# SM1_System.net
KiCad netlist of a schematic drawn in Altium Designer
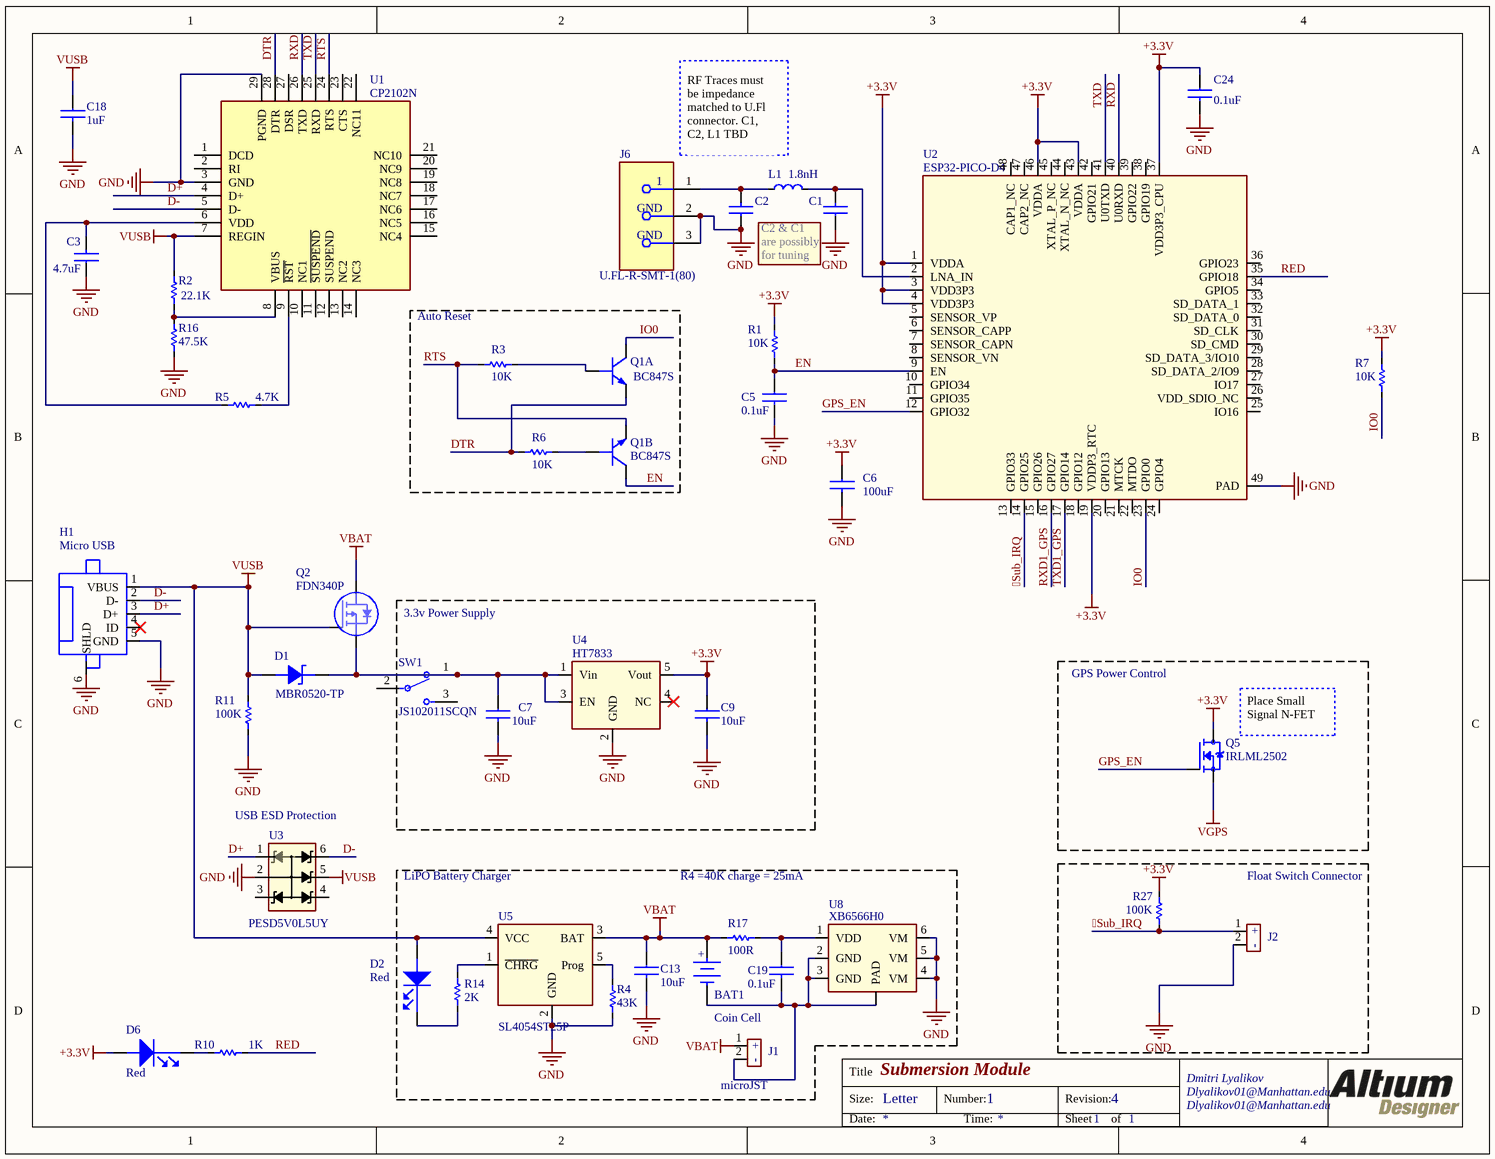
[diagram p0: SM1_System.SchDoc]

(export (version "E")
  (design (tool "Eeschema 10.0.6"))
  (components
    (comp (ref "BAT1")
      (value "BATTERY-HOLDER (2450)")
      (footprint "BU2450SM-JJ-GTR")
      (description "HOLDER,BATT,COIN,24.5MM,SMT")
      (fields (field (name "PARTNUMBER") "BU2450SM-JJ-GTR") (field (name "MANUFACTURER") "MPD"))
      (libsource (lib "MAR") (part "BU2450SM-JJ-GTR"))
    )
    (comp (ref "C1")
      (value "~")
      (footprint "CAPC1005X56N")
      (description "DNP")
      (libsource (lib "MAR") (part "CAP_0402"))
    )
    (comp (ref "C2")
      (value "~")
      (footprint "CAPC1005X56N")
      (description "DNP")
      (libsource (lib "MAR") (part "CAP_0402"))
    )
    (comp (ref "C3")
      (value "4.7uF")
      (footprint "CAPC1005X56N")
      (description "CAP CER 4.7uF 16V 0402")
      (fields (field (name "PARTNUMBER") "CM05X5R475M16AH") (field (name "MANUFACTURER") "Kyocera"))
      (libsource (lib "Parts_Library") (part "CAP_0603"))
    )
    (comp (ref "C5")
      (value "0.1uF")
      (footprint "CAPC1005X56N")
      (description "CAP CER 0.1uF 16V 0402")
      (fields (field (name "PARTNUMBER") "TCC0402X5R104M160AT") (field (name "MANUFACTURER") "CCTC"))
      (libsource (lib "MAR") (part "CAP_0402"))
    )
    (comp (ref "C6")
      (value "100uF")
      (footprint "CAPC3216X160L")
      (description "CAP CER 100uF 6.3V 1206")
      (fields (field (name "PARTNUMBER") "JMK316BJ107ML-T") (field (name "MANUFACTURER") "Taiyo Yuden"))
      (libsource (lib "MAR") (part "CAP_1206"))
    )
    (comp (ref "C7")
      (value "10uF")
      (footprint "CAPC2012X140N")
      (description "CAP 10uF 0805")
      (fields (field (name "MANUFACTURER") "Murata") (field (name "PARTNUMBER") "GRM21BB31C106KE15L"))
      (libsource (lib "MAR") (part "CAP_0805"))
    )
    (comp (ref "C9")
      (value "10uF")
      (footprint "CAPC2012X140N")
      (description "CAP 10uF 0805")
      (fields (field (name "MANUFACTURER") "Murata") (field (name "PARTNUMBER") "GRM21BB31C106KE15L"))
      (libsource (lib "MAR") (part "CAP_0805"))
    )
    (comp (ref "C13")
      (value "10uF")
      (footprint "CAPC2012X140N")
      (description "CAP CER 10uF 16V 0805")
      (fields (field (name "PARTNUMBER") "CL21A106KOQNNNG") (field (name "MANUFACTURER") "Samsung"))
      (libsource (lib "MAR") (part "CAP_0805"))
    )
    (comp (ref "C18")
      (value "1uF")
      (footprint "CAPC1005X56N")
      (description "CAP CER 1uF 16V 0402")
      (fields (field (name "PARTNUMBER") "GRM155R61C105KA12D") (field (name "MANUFACTURER") "Murata"))
      (libsource (lib "MAR") (part "CAP_0603"))
    )
    (comp (ref "C19")
      (value "0.1uF")
      (footprint "CAPC1005X56N")
      (description "CAP CER 0.1uF 16V 0402")
      (fields (field (name "PARTNUMBER") "TCC0402X5R104M160AT") (field (name "MANUFACTURER") "CCTC"))
      (libsource (lib "MAR") (part "CAP_0402"))
    )
    (comp (ref "C24")
      (value "0.1uF")
      (footprint "CAPC1005X56N")
      (description "CAP CER 0.1uF 16V 0402")
      (fields (field (name "PARTNUMBER") "TCC0402X5R104M160AT") (field (name "MANUFACTURER") "CCTC"))
      (libsource (lib "MAR") (part "CAP_0402"))
    )
    (comp (ref "D1")
      (value "MBR0520-TP")
      (footprint "SOD123")
      (description "DIODE SCHOTTKY 20V 500MA SOD123")
      (fields (field (name "MANUFACTURER") "CJ") (field (name "PARTNUMBER") "MBR0520"))
      (libsource (lib "MAR") (part "MBR0520-TP"))
    )
    (comp (ref "D2")
      (value "Red")
      (footprint "LED1608X55N-RED")
      (description "LED RED CLEAR 0603 SMD")
      (fields (field (name "MANUFACTURER") "FNO") (field (name "PARTNUMBER") "FC-DA1608HRK-620D"))
      (libsource (lib "MAR") (part "LED_0603"))
    )
    (comp (ref "D6")
      (value "Red")
      (footprint "LED1608X55N-RED")
      (description "LED RED CLEAR 0603 SMD")
      (fields (field (name "MANUFACTURER") "FNO") (field (name "PARTNUMBER") "FC-DA1608HRK-620D"))
      (libsource (lib "MAR") (part "LED_0603"))
    )
    (comp (ref "H1")
      (value "Micro USB")
      (footprint "1981584-1")
      (description "CONN RCPT MICRO USB TYPE AB")
      (fields (field (name "MANUFACTURER") "REG CON") (field (name "PARTNUMBER") "C21377"))
      (libsource (lib "MAR") (part "1981584-1"))
    )
    (comp (ref "J1")
      (value "CON2")
      (footprint "JST_Micro_2PIN")
      (description "JST MIcro CONN 2POS")
      (libsource (lib "MAR") (part "JST_Micro_CONN_2PIN"))
    )
    (comp (ref "J2")
      (value "CON2")
      (footprint "JST_Micro_2PIN")
      (description "JST MIcro CONN 2POS")
      (libsource (lib "MAR") (part "JST_Micro_CONN_2PIN"))
    )
    (comp (ref "J6")
      (value "U.FL-R-SMT-1(80)")
      (footprint "FP-U_FL-R-SMT-1_80-MFG")
      (description "CONN U.FL RCPT STR 50 OHM SMD")
      (libsource (lib "Altium Content Vault") (part "ad010367dc7cd7c7a13299a56582dd6"))
    )
    (comp (ref "L1")
      (value "1.8nH")
      (footprint "RESC1005X40L")
      (description "Inductor 1.8nH 0402")
      (fields (field (name "PARTNUMBER") "BKW0603UC1N8KGT") (field (name "MANUFACTURER") "GFBE"))
      (libsource (lib "MAR") (part "Inductor"))
    )
    (comp (ref "Q1")
      (value "BC847S")
      (footprint "SOT65P210X110-6N")
      (description "TRANS 2NPN 44V 0.1A SC-70-6")
      (fields (field (name "MANUFACTURER") "Changjiang") (field (name "PARTNUMBER") "BC847S"))
      (libsource (lib "MAR") (part "BC847S"))
    )
    (comp (ref "Q2")
      (value "FDN340P")
      (footprint "SOT95P240X110-3N")
      (description "MOSFET P-CH 20V 2A SOT-23")
      (fields (field (name "MANUFACTURER") "On Semi") (field (name "PARTNUMBER") "FDN340P"))
      (libsource (lib "MAR") (part "FDN340P"))
    )
    (comp (ref "Q5")
      (value "IRLML2502")
      (footprint "SOT95P237X112-3N")
      (description "N-Channel 20 V 4.2A (Ta) 1.25W (Ta) Surface Mount Micro3Ã¢â€žÂ¢ /SOT-23")
      (fields (field (name "MF") "Infineon Technologies"))
      (libsource (lib "IRLML2502") (part "IRLML2502"))
    )
    (comp (ref "R1")
      (value "10K")
      (footprint "RESC1005X40L")
      (description "RES SMD 10K OHM 0402")
      (fields (field (name "PARTNUMBER") "RC-02W1002FT") (field (name "MANUFACTURER") "Guangdong"))
      (libsource (lib "MAR") (part "RES_0402"))
    )
    (comp (ref "R2")
      (value "22.1K")
      (footprint "RESC1005X40L")
      (description "RES SMD 22.1K OHM 0402")
      (fields (field (name "MANUFACTURER") "Yageo") (field (name "PARTNUMBER") "RC0402FR-0722K1L"))
      (libsource (lib "MAR") (part "RES_0603"))
    )
    (comp (ref "R3")
      (value "10K")
      (footprint "RESC1005X40L")
      (description "RES SMD 10K OHM 0402")
      (fields (field (name "PARTNUMBER") "RC-02W1002FT") (field (name "MANUFACTURER") "Guangdong"))
      (libsource (lib "MAR") (part "RES_0402"))
    )
    (comp (ref "R4")
      (value "43K")
      (footprint "RESC1005X40L")
      (description "RES SMD 43K OHM 0402")
      (fields (field (name "MANUFACTURER") "Uniroyal") (field (name "PARTNUMBER") "0402WGF4302TCE"))
      (libsource (lib "MAR") (part "RES_0603"))
    )
    (comp (ref "R5")
      (value "4.7K")
      (footprint "RESC1005X40L")
      (description "RES SMD 4.7K OHM 0402")
      (fields (field (name "MANUFACTURER") "Yageo") (field (name "PARTNUMBER") "RC0402FR-074K7L"))
      (libsource (lib "MAR") (part "RES_0603"))
    )
    (comp (ref "R6")
      (value "10K")
      (footprint "RESC1005X40L")
      (description "RES SMD 10K OHM 0402")
      (fields (field (name "PARTNUMBER") "RC-02W1002FT") (field (name "MANUFACTURER") "Guangdong"))
      (libsource (lib "MAR") (part "RES_0402"))
    )
    (comp (ref "R7")
      (value "10K")
      (footprint "RESC1005X40L")
      (description "RES SMD 10K OHM 0402")
      (fields (field (name "PARTNUMBER") "RC-02W1002FT") (field (name "MANUFACTURER") "Guangdong"))
      (libsource (lib "MAR") (part "RES_0402"))
    )
    (comp (ref "R10")
      (value "1K")
      (footprint "RESC1005X40L")
      (description "RES SMD 1K OHM 0402")
      (fields (field (name "PARTNUMBER") "RC0402FR-071KL") (field (name "MANUFACTURER") "Yageo"))
      (libsource (lib "MAR") (part "RES_0402"))
    )
    (comp (ref "R11")
      (value "100K")
      (footprint "RESC1005X40L")
      (description "RES SMD 100K OHM 0402")
      (fields (field (name "MANUFACTURER") "Uniroyal Elec") (field (name "PARTNUMBER") "0402WGF1003TCE"))
      (libsource (lib "MAR") (part "RES_0603"))
    )
    (comp (ref "R14")
      (value "2K")
      (footprint "RESC1005X40L")
      (description "RES SMD 2K OHM 1% 1/10W 0402")
      (fields (field (name "MANUFACTURER") "LIZ Elec") (field (name "PARTNUMBER") "CR0402FF2001G"))
      (libsource (lib "MAR") (part "RES_0603"))
    )
    (comp (ref "R16")
      (value "47.5K")
      (footprint "RESC1005X40L")
      (description "RES SMD 47.5K OHM 0402")
      (fields (field (name "MANUFACTURER") "Yageo") (field (name "PARTNUMBER") "RC0402FR-0747K5L"))
      (libsource (lib "MAR") (part "RES_0603"))
    )
    (comp (ref "R17")
      (value "100R")
      (footprint "RESC1005X40L")
      (description "RES SMD 100R OHM 1% 1/10W 0402")
      (fields (field (name "MANUFACTURER") "Yageo") (field (name "PARTNUMBER") "RC0402FR-07100RL"))
      (libsource (lib "MAR") (part "RES_0603"))
    )
    (comp (ref "R27")
      (value "100K")
      (footprint "RESC1005X40L")
      (description "RES SMD 10K OHM 0402")
      (fields (field (name "PARTNUMBER") "RC-02W1002FT") (field (name "MANUFACTURER") "Guangdong"))
      (libsource (lib "MAR") (part "RES_0402"))
    )
    (comp (ref "SW1")
      (value "JS102011SCQN")
      (footprint "FP-JS102011SCQN-MFG")
      (description "SWITCH SLIDE SPDT 300MA 6V")
      (libsource (lib "Altium Content Vault") (part "39e195cbbadc85d1df0d7eb6847d379"))
    )
    (comp (ref "U1")
      (value "CP2102N")
      (footprint "28-QFN")
      (description "IC BRIDGE USB TO UART 28QFN")
      (fields (field (name "MANUFACTURER") "Silicon Labs") (field (name "PARTNUMBER") "CP2102N-A01-GQFN28"))
      (libsource (lib "MAR") (part "CP2102N"))
    )
    (comp (ref "U2")
      (value "ESP32-PICO-D4")
      (footprint "QFN48")
      (description "RF Transceiver ICs QFN-48_7x7x05P RoHS")
      (fields (field (name "MANUFACTURER") "Espressif"))
      (libsource (lib "MAR") (part "ESP32-PICO-D4"))
    )
    (comp (ref "U3")
      (value "PESD5V0L5UY")
      (footprint "SOT65P210X110-6N")
      (description "TVS SOT-363 RoHS")
      (fields (field (name "MANUFACTURER") "Yenji") (field (name "PARTNUMBER") "PESD5V0L5UY"))
      (libsource (lib "MAR") (part "PESD5V0L5UY"))
    )
    (comp (ref "U4")
      (value "HT7833")
      (footprint "SOT95P280X144-5N")
      (description "IC LDO 3.3V 0.5A SOT23-5")
      (fields (field (name "MANUFACTURER") "Holtek") (field (name "PARTNUMBER") "HT7833"))
      (libsource (lib "Schematic_Library") (part "HT7833"))
    )
    (comp (ref "U5")
      (value "SL4054ST25P")
      (footprint "SOT95P280X144-5N")
      (description "Charger IC Lithium-Ion/Polymer SOT23-5")
      (fields (field (name "MANUFACTURER") "Techfuse"))
      (libsource (lib "Schematic_Library") (part "SL4054ST25P"))
    )
    (comp (ref "U8")
      (value "XB6566H0")
      (footprint "DFN-6 2x2mm")
      (description "IC Battery Protection")
      (fields (field (name "MANUFACTURER") "XySemi") (field (name "PARTNUMBER") "XB6566H0"))
      (libsource (lib "MAR") (part "XB6566H0"))
    )
  )
  (nets
    (net (code "1") (name "+3.3V") (class "Default")
      (node (ref "C24") (pin "1") (pinfunction "1_1") (pintype "passive"))
      (node (ref "C6") (pin "1") (pinfunction "1_1") (pintype "passive"))
      (node (ref "C9") (pin "1") (pinfunction "1_1") (pintype "passive"))
      (node (ref "D6") (pin "2") (pinfunction "ANODE_2") (pintype "passive"))
      (node (ref "Q5") (pin "3") (pinfunction "D_3") (pintype "passive"))
      (node (ref "R1") (pin "1") (pintype "passive"))
      (node (ref "R27") (pin "1") (pintype "passive"))
      (node (ref "R7") (pin "1") (pintype "passive"))
      (node (ref "U2") (pin "1") (pinfunction "VDDA_1") (pintype "power_in"))
      (node (ref "U2") (pin "19") (pinfunction "VDDP3_RTC_19") (pintype "passive"))
      (node (ref "U2") (pin "3") (pinfunction "VDD3P3_3") (pintype "power_in"))
      (node (ref "U2") (pin "37") (pinfunction "VDD3P3_CPU_37") (pintype "power_in"))
      (node (ref "U2") (pin "4") (pinfunction "VDD3P3_4") (pintype "power_in"))
      (node (ref "U2") (pin "43") (pinfunction "VDDA_43") (pintype "power_in"))
      (node (ref "U2") (pin "46") (pinfunction "VDDA_46") (pintype "power_in"))
      (node (ref "U4") (pin "5") (pinfunction "Vout_5") (pintype "passive"))
    )
    (net (code "2") (name "/Sub_IRQ") (class "Default")
      (node (ref "J2") (pin "1") (pintype "passive"))
      (node (ref "R27") (pin "2") (pintype "passive"))
      (node (ref "U2") (pin "14") (pinfunction "GPIO25_14") (pintype "passive"))
    )
    (net (code "3") (name "/D+") (class "Default")
      (node (ref "H1") (pin "3") (pinfunction "D+_3") (pintype "passive"))
      (node (ref "U1") (pin "4") (pinfunction "D+_4") (pintype "passive"))
      (node (ref "U3") (pin "1") (pinfunction "1_1") (pintype "passive"))
    )
    (net (code "4") (name "/D-") (class "Default")
      (node (ref "H1") (pin "2") (pinfunction "D-_2") (pintype "passive"))
      (node (ref "U1") (pin "5") (pinfunction "D-_5") (pintype "passive"))
      (node (ref "U3") (pin "6") (pinfunction "6_6") (pintype "passive"))
    )
    (net (code "5") (name "/DTR") (class "Default")
      (node (ref "Q1") (pin "1") (pinfunction "E1_1") (pintype "passive"))
      (node (ref "R6") (pin "2") (pintype "passive"))
      (node (ref "U1") (pin "28") (pinfunction "DTR_28") (pintype "passive"))
    )
    (net (code "6") (name "/EN") (class "Default")
      (node (ref "C5") (pin "1") (pinfunction "1_1") (pintype "passive"))
      (node (ref "Q1") (pin "3") (pinfunction "C2_3") (pintype "passive"))
      (node (ref "R1") (pin "2") (pintype "passive"))
      (node (ref "U2") (pin "9") (pinfunction "EN_9") (pintype "passive"))
    )
    (net (code "7") (name "/GPS_EN") (class "Default")
      (node (ref "Q5") (pin "1") (pinfunction "G_1") (pintype "passive"))
      (node (ref "U2") (pin "12") (pinfunction "GPIO32_12") (pintype "passive"))
    )
    (net (code "8") (name "/IO0") (class "Default")
      (node (ref "Q1") (pin "6") (pinfunction "C1_6") (pintype "passive"))
      (node (ref "R7") (pin "2") (pintype "passive"))
      (node (ref "U2") (pin "23") (pinfunction "GPIO0_23") (pintype "passive"))
    )
    (net (code "9") (name "/RED") (class "Default")
      (node (ref "R10") (pin "2") (pintype "passive"))
      (node (ref "U2") (pin "35") (pinfunction "GPIO18_35") (pintype "passive"))
    )
    (net (code "10") (name "/RTS") (class "Default")
      (node (ref "Q1") (pin "4") (pinfunction "E2_4") (pintype "passive"))
      (node (ref "R3") (pin "2") (pintype "passive"))
      (node (ref "U1") (pin "24") (pinfunction "RTS_24") (pintype "passive"))
    )
    (net (code "11") (name "/RXD") (class "Default")
      (node (ref "U1") (pin "26") (pinfunction "TXD_26") (pintype "passive"))
      (node (ref "U2") (pin "40") (pinfunction "U0RXD_40") (pintype "passive"))
    )
    (net (code "12") (name "/RXD1_GPS") (class "Default")
      (node (ref "U2") (pin "16") (pinfunction "GPIO27_16") (pintype "passive"))
    )
    (net (code "13") (name "/TXD") (class "Default")
      (node (ref "U1") (pin "25") (pinfunction "RXD_25") (pintype "passive"))
      (node (ref "U2") (pin "41") (pinfunction "U0TXD_41") (pintype "passive"))
    )
    (net (code "14") (name "/TXD1_GPS") (class "Default")
      (node (ref "U2") (pin "17") (pinfunction "GPIO14_17") (pintype "passive"))
    )
    (net (code "15") (name "GND") (class "Default")
      (node (ref "C1") (pin "1") (pinfunction "1_1") (pintype "passive"))
      (node (ref "C13") (pin "2") (pinfunction "2_2") (pintype "passive"))
      (node (ref "C18") (pin "2") (pinfunction "2_2") (pintype "passive"))
      (node (ref "C2") (pin "1") (pinfunction "1_1") (pintype "passive"))
      (node (ref "C24") (pin "2") (pinfunction "2_2") (pintype "passive"))
      (node (ref "C3") (pin "1") (pinfunction "1_1") (pintype "passive"))
      (node (ref "C5") (pin "2") (pinfunction "2_2") (pintype "passive"))
      (node (ref "C6") (pin "2") (pinfunction "2_2") (pintype "passive"))
      (node (ref "C7") (pin "2") (pinfunction "2_2") (pintype "passive"))
      (node (ref "C9") (pin "2") (pinfunction "2_2") (pintype "passive"))
      (node (ref "H1") (pin "5") (pinfunction "GND_5") (pintype "power_in"))
      (node (ref "H1") (pin "6") (pinfunction "SHLD_6") (pintype "power_in"))
      (node (ref "J2") (pin "2") (pintype "passive"))
      (node (ref "J6") (pin "2") (pinfunction "GND_2") (pintype "power_in"))
      (node (ref "J6") (pin "3") (pinfunction "GND_3") (pintype "power_in"))
      (node (ref "R11") (pin "2") (pintype "passive"))
      (node (ref "R16") (pin "1") (pintype "passive"))
      (node (ref "R4") (pin "2") (pintype "passive"))
      (node (ref "U1") (pin "29") (pinfunction "PGND_29") (pintype "passive"))
      (node (ref "U1") (pin "3") (pinfunction "GND_3") (pintype "power_in"))
      (node (ref "U2") (pin "49") (pinfunction "PAD_49") (pintype "power_in"))
      (node (ref "U3") (pin "2") (pinfunction "2_2") (pintype "passive"))
      (node (ref "U4") (pin "2") (pinfunction "GND_2") (pintype "power_in"))
      (node (ref "U5") (pin "2") (pinfunction "GND_2") (pintype "power_in"))
      (node (ref "U8") (pin "4") (pinfunction "VM_4") (pintype "passive"))
      (node (ref "U8") (pin "5") (pinfunction "VM_5") (pintype "passive"))
      (node (ref "U8") (pin "6") (pinfunction "VM_6") (pintype "passive"))
    )
    (net (code "16") (name "Net-(BAT1--)") (class "Default")
      (node (ref "BAT1") (pin "2") (pinfunction "-_2") (pintype "power_in"))
      (node (ref "C19") (pin "2") (pinfunction "2_2") (pintype "passive"))
      (node (ref "J1") (pin "2") (pintype "passive"))
      (node (ref "U8") (pin "2") (pinfunction "GND_2") (pintype "power_in"))
      (node (ref "U8") (pin "3") (pinfunction "GND_3") (pintype "power_in"))
      (node (ref "U8") (pin "7") (pinfunction "PAD_7") (pintype "passive"))
    )
    (net (code "17") (name "Net-(C2-Pad2)") (class "Default")
      (node (ref "C2") (pin "2") (pinfunction "2_2") (pintype "passive"))
      (node (ref "J6") (pin "1") (pinfunction "1_1") (pintype "passive"))
      (node (ref "L1") (pin "1") (pinfunction "1_1") (pintype "passive"))
    )
    (net (code "18") (name "Net-(D1-Cathode)") (class "Default")
      (node (ref "C7") (pin "1") (pinfunction "1_1") (pintype "passive"))
      (node (ref "D1") (pin "1") (pinfunction "Cathode_1") (pintype "passive"))
      (node (ref "Q2") (pin "2") (pinfunction "S_2") (pintype "passive"))
      (node (ref "SW1") (pin "1") (pinfunction "1_1") (pintype "passive"))
      (node (ref "U4") (pin "1") (pinfunction "Vin_1") (pintype "passive"))
      (node (ref "U4") (pin "3") (pinfunction "EN_3") (pintype "passive"))
    )
    (net (code "19") (name "Net-(D2-CATHODE)") (class "Default")
      (node (ref "D2") (pin "1") (pinfunction "CATHODE_1") (pintype "passive"))
      (node (ref "R14") (pin "1") (pintype "passive"))
    )
    (net (code "20") (name "Net-(D6-CATHODE)") (class "Default")
      (node (ref "D6") (pin "1") (pinfunction "CATHODE_1") (pintype "passive"))
      (node (ref "R10") (pin "1") (pintype "passive"))
    )
    (net (code "21") (name "Net-(Q1A-B1)") (class "Default")
      (node (ref "Q1") (pin "2") (pinfunction "B1_2") (pintype "passive"))
      (node (ref "R3") (pin "1") (pintype "passive"))
    )
    (net (code "22") (name "Net-(Q1B-B2)") (class "Default")
      (node (ref "Q1") (pin "5") (pinfunction "B2_5") (pintype "passive"))
      (node (ref "R6") (pin "1") (pintype "passive"))
    )
    (net (code "23") (name "Net-(U1-VBUS)") (class "Default")
      (node (ref "R16") (pin "2") (pintype "passive"))
      (node (ref "R2") (pin "1") (pintype "passive"))
      (node (ref "U1") (pin "8") (pinfunction "VBUS_8") (pintype "power_in"))
    )
    (net (code "24") (name "Net-(U1-VDD)") (class "Default")
      (node (ref "C3") (pin "2") (pinfunction "2_2") (pintype "passive"))
      (node (ref "R5") (pin "1") (pintype "passive"))
      (node (ref "U1") (pin "6") (pinfunction "VDD_6") (pintype "power_in"))
    )
    (net (code "25") (name "Net-(U1-~{RST})") (class "Default")
      (node (ref "R5") (pin "2") (pintype "passive"))
      (node (ref "U1") (pin "9") (pinfunction "~{RST}_9") (pintype "passive"))
    )
    (net (code "26") (name "Net-(U2-LNA_IN)") (class "Default")
      (node (ref "C1") (pin "2") (pinfunction "2_2") (pintype "passive"))
      (node (ref "L1") (pin "2") (pinfunction "2_2") (pintype "passive"))
      (node (ref "U2") (pin "2") (pinfunction "LNA_IN_2") (pintype "passive"))
    )
    (net (code "27") (name "Net-(U5-Prog)") (class "Default")
      (node (ref "R4") (pin "1") (pintype "passive"))
      (node (ref "U5") (pin "5") (pinfunction "Prog_5") (pintype "passive"))
    )
    (net (code "28") (name "Net-(U5-~{CHRG})") (class "Default")
      (node (ref "R14") (pin "2") (pintype "passive"))
      (node (ref "U5") (pin "1") (pinfunction "~{CHRG}_1") (pintype "passive"))
    )
    (net (code "29") (name "Net-(U8-VDD)") (class "Default")
      (node (ref "C19") (pin "1") (pinfunction "1_1") (pintype "passive"))
      (node (ref "R17") (pin "2") (pintype "passive"))
      (node (ref "U8") (pin "1") (pinfunction "VDD_1") (pintype "power_in"))
    )
    (net (code "30") (name "VBAT") (class "Default")
      (node (ref "BAT1") (pin "1") (pinfunction "+_1") (pintype "power_in"))
      (node (ref "C13") (pin "1") (pinfunction "1_1") (pintype "passive"))
      (node (ref "J1") (pin "1") (pintype "passive"))
      (node (ref "Q2") (pin "3") (pinfunction "D_3") (pintype "passive"))
      (node (ref "R17") (pin "1") (pintype "passive"))
      (node (ref "U5") (pin "3") (pinfunction "BAT_3") (pintype "passive"))
    )
    (net (code "31") (name "VGPS") (class "Default")
      (node (ref "Q5") (pin "2") (pinfunction "S_2") (pintype "passive"))
    )
    (net (code "32") (name "VUSB") (class "Default")
      (node (ref "C18") (pin "1") (pinfunction "1_1") (pintype "passive"))
      (node (ref "D1") (pin "2") (pinfunction "Annode_2") (pintype "passive"))
      (node (ref "D2") (pin "2") (pinfunction "ANODE_2") (pintype "passive"))
      (node (ref "H1") (pin "1") (pinfunction "VBUS_1") (pintype "power_in"))
      (node (ref "Q2") (pin "1") (pinfunction "G_1") (pintype "passive"))
      (node (ref "R11") (pin "1") (pintype "passive"))
      (node (ref "R2") (pin "2") (pintype "passive"))
      (node (ref "U1") (pin "7") (pinfunction "REGIN_7") (pintype "passive"))
      (node (ref "U3") (pin "5") (pinfunction "5_5") (pintype "passive"))
      (node (ref "U5") (pin "4") (pinfunction "VCC_4") (pintype "passive"))
    )
    (net (code "33") (name "unconnected-(H1-ID-Pad4)") (class "Default")
      (node (ref "H1") (pin "4") (pinfunction "ID_4") (pintype "passive+no_connect"))
    )
    (net (code "34") (name "unconnected-(SW1-C-Pad2)") (class "Default")
      (node (ref "SW1") (pin "2") (pinfunction "C_2") (pintype "passive"))
    )
    (net (code "35") (name "unconnected-(SW1-Pad3)") (class "Default")
      (node (ref "SW1") (pin "3") (pinfunction "3_3") (pintype "passive"))
    )
    (net (code "36") (name "unconnected-(U1-CTS-Pad23)") (class "Default")
      (node (ref "U1") (pin "23") (pinfunction "CTS_23") (pintype "passive"))
    )
    (net (code "37") (name "unconnected-(U1-DCD-Pad1)") (class "Default")
      (node (ref "U1") (pin "1") (pinfunction "DCD_1") (pintype "passive"))
    )
    (net (code "38") (name "unconnected-(U1-DSR-Pad27)") (class "Default")
      (node (ref "U1") (pin "27") (pinfunction "DSR_27") (pintype "passive"))
    )
    (net (code "39") (name "unconnected-(U1-NC1-Pad10)") (class "Default")
      (node (ref "U1") (pin "10") (pinfunction "NC1_10") (pintype "passive"))
    )
    (net (code "40") (name "unconnected-(U1-NC2-Pad13)") (class "Default")
      (node (ref "U1") (pin "13") (pinfunction "NC2_13") (pintype "passive"))
    )
    (net (code "41") (name "unconnected-(U1-NC3-Pad14)") (class "Default")
      (node (ref "U1") (pin "14") (pinfunction "NC3_14") (pintype "passive"))
    )
    (net (code "42") (name "unconnected-(U1-NC4-Pad15)") (class "Default")
      (node (ref "U1") (pin "15") (pinfunction "NC4_15") (pintype "passive"))
    )
    (net (code "43") (name "unconnected-(U1-NC5-Pad16)") (class "Default")
      (node (ref "U1") (pin "16") (pinfunction "NC5_16") (pintype "passive"))
    )
    (net (code "44") (name "unconnected-(U1-NC6-Pad17)") (class "Default")
      (node (ref "U1") (pin "17") (pinfunction "NC6_17") (pintype "passive"))
    )
    (net (code "45") (name "unconnected-(U1-NC7-Pad18)") (class "Default")
      (node (ref "U1") (pin "18") (pinfunction "NC7_18") (pintype "passive"))
    )
    (net (code "46") (name "unconnected-(U1-NC8-Pad19)") (class "Default")
      (node (ref "U1") (pin "19") (pinfunction "NC8_19") (pintype "passive"))
    )
    (net (code "47") (name "unconnected-(U1-NC9-Pad20)") (class "Default")
      (node (ref "U1") (pin "20") (pinfunction "NC9_20") (pintype "passive"))
    )
    (net (code "48") (name "unconnected-(U1-NC10-Pad21)") (class "Default")
      (node (ref "U1") (pin "21") (pinfunction "NC10_21") (pintype "passive"))
    )
    (net (code "49") (name "unconnected-(U1-NC11-Pad22)") (class "Default")
      (node (ref "U1") (pin "22") (pinfunction "NC11_22") (pintype "passive"))
    )
    (net (code "50") (name "unconnected-(U1-RI-Pad2)") (class "Default")
      (node (ref "U1") (pin "2") (pinfunction "RI_2") (pintype "passive"))
    )
    (net (code "51") (name "unconnected-(U1-SUSPEND-Pad12)") (class "Default")
      (node (ref "U1") (pin "12") (pinfunction "SUSPEND_12") (pintype "passive"))
    )
    (net (code "52") (name "unconnected-(U1-~{SUSPEND}-Pad11)") (class "Default")
      (node (ref "U1") (pin "11") (pinfunction "~{SUSPEND}_11") (pintype "passive"))
    )
    (net (code "53") (name "unconnected-(U2-CAP1_NC-Pad48)") (class "Default")
      (node (ref "U2") (pin "48") (pinfunction "CAP1_NC_48") (pintype "passive"))
    )
    (net (code "54") (name "unconnected-(U2-CAP2_NC-Pad47)") (class "Default")
      (node (ref "U2") (pin "47") (pinfunction "CAP2_NC_47") (pintype "passive"))
    )
    (net (code "55") (name "unconnected-(U2-GPIO4-Pad24)") (class "Default")
      (node (ref "U2") (pin "24") (pinfunction "GPIO4_24") (pintype "passive"))
    )
    (net (code "56") (name "unconnected-(U2-GPIO5-Pad34)") (class "Default")
      (node (ref "U2") (pin "34") (pinfunction "GPIO5_34") (pintype "passive"))
    )
    (net (code "57") (name "unconnected-(U2-GPIO12-Pad18)") (class "Default")
      (node (ref "U2") (pin "18") (pinfunction "GPIO12_18") (pintype "passive"))
    )
    (net (code "58") (name "unconnected-(U2-GPIO13-Pad20)") (class "Default")
      (node (ref "U2") (pin "20") (pinfunction "GPIO13_20") (pintype "passive"))
    )
    (net (code "59") (name "unconnected-(U2-GPIO19-Pad38)") (class "Default")
      (node (ref "U2") (pin "38") (pinfunction "GPIO19_38") (pintype "passive"))
    )
    (net (code "60") (name "unconnected-(U2-GPIO21-Pad42)") (class "Default")
      (node (ref "U2") (pin "42") (pinfunction "GPIO21_42") (pintype "passive"))
    )
    (net (code "61") (name "unconnected-(U2-GPIO22-Pad39)") (class "Default")
      (node (ref "U2") (pin "39") (pinfunction "GPIO22_39") (pintype "passive"))
    )
    (net (code "62") (name "unconnected-(U2-GPIO23-Pad36)") (class "Default")
      (node (ref "U2") (pin "36") (pinfunction "GPIO23_36") (pintype "passive"))
    )
    (net (code "63") (name "unconnected-(U2-GPIO26-Pad15)") (class "Default")
      (node (ref "U2") (pin "15") (pinfunction "GPIO26_15") (pintype "passive"))
    )
    (net (code "64") (name "unconnected-(U2-GPIO33-Pad13)") (class "Default")
      (node (ref "U2") (pin "13") (pinfunction "GPIO33_13") (pintype "passive"))
    )
    (net (code "65") (name "unconnected-(U2-GPIO34-Pad10)") (class "Default")
      (node (ref "U2") (pin "10") (pinfunction "GPIO34_10") (pintype "passive"))
    )
    (net (code "66") (name "unconnected-(U2-GPIO35-Pad11)") (class "Default")
      (node (ref "U2") (pin "11") (pinfunction "GPIO35_11") (pintype "passive"))
    )
    (net (code "67") (name "unconnected-(U2-IO16-Pad25)") (class "Default")
      (node (ref "U2") (pin "25") (pinfunction "IO16_25") (pintype "passive"))
    )
    (net (code "68") (name "unconnected-(U2-IO17-Pad27)") (class "Default")
      (node (ref "U2") (pin "27") (pinfunction "IO17_27") (pintype "passive"))
    )
    (net (code "69") (name "unconnected-(U2-MTCK-Pad21)") (class "Default")
      (node (ref "U2") (pin "21") (pinfunction "MTCK_21") (pintype "passive"))
    )
    (net (code "70") (name "unconnected-(U2-MTDO-Pad22)") (class "Default")
      (node (ref "U2") (pin "22") (pinfunction "MTDO_22") (pintype "passive"))
    )
    (net (code "71") (name "unconnected-(U2-SD_CLK-Pad31)") (class "Default")
      (node (ref "U2") (pin "31") (pinfunction "SD_CLK_31") (pintype "passive"))
    )
    (net (code "72") (name "unconnected-(U2-SD_CMD-Pad30)") (class "Default")
      (node (ref "U2") (pin "30") (pinfunction "SD_CMD_30") (pintype "passive"))
    )
    (net (code "73") (name "unconnected-(U2-SD_DATA_0-Pad32)") (class "Default")
      (node (ref "U2") (pin "32") (pinfunction "SD_DATA_0_32") (pintype "passive"))
    )
    (net (code "74") (name "unconnected-(U2-SD_DATA_1-Pad33)") (class "Default")
      (node (ref "U2") (pin "33") (pinfunction "SD_DATA_1_33") (pintype "passive"))
    )
    (net (code "75") (name "unconnected-(U2-SD_DATA_2{slash}IO9-Pad28)") (class "Default")
      (node (ref "U2") (pin "28") (pinfunction "SD_DATA_2/IO9_28") (pintype "passive"))
    )
    (net (code "76") (name "unconnected-(U2-SD_DATA_3{slash}IO10-Pad29)") (class "Default")
      (node (ref "U2") (pin "29") (pinfunction "SD_DATA_3/IO10_29") (pintype "passive"))
    )
    (net (code "77") (name "unconnected-(U2-SENSOR_CAPN-Pad7)") (class "Default")
      (node (ref "U2") (pin "7") (pinfunction "SENSOR_CAPN_7") (pintype "passive"))
    )
    (net (code "78") (name "unconnected-(U2-SENSOR_CAPP-Pad6)") (class "Default")
      (node (ref "U2") (pin "6") (pinfunction "SENSOR_CAPP_6") (pintype "passive"))
    )
    (net (code "79") (name "unconnected-(U2-SENSOR_VN-Pad8)") (class "Default")
      (node (ref "U2") (pin "8") (pinfunction "SENSOR_VN_8") (pintype "passive"))
    )
    (net (code "80") (name "unconnected-(U2-SENSOR_VP-Pad5)") (class "Default")
      (node (ref "U2") (pin "5") (pinfunction "SENSOR_VP_5") (pintype "passive"))
    )
    (net (code "81") (name "unconnected-(U2-VDD_SDIO_NC-Pad26)") (class "Default")
      (node (ref "U2") (pin "26") (pinfunction "VDD_SDIO_NC_26") (pintype "power_in"))
    )
    (net (code "82") (name "unconnected-(U2-XTAL_N_NC-Pad44)") (class "Default")
      (node (ref "U2") (pin "44") (pinfunction "XTAL_N_NC_44") (pintype "passive"))
    )
    (net (code "83") (name "unconnected-(U2-XTAL_P_NC-Pad45)") (class "Default")
      (node (ref "U2") (pin "45") (pinfunction "XTAL_P_NC_45") (pintype "passive"))
    )
    (net (code "84") (name "unconnected-(U3-Pad3)") (class "Default")
      (node (ref "U3") (pin "3") (pinfunction "3_3") (pintype "passive"))
    )
    (net (code "85") (name "unconnected-(U3-Pad4)") (class "Default")
      (node (ref "U3") (pin "4") (pinfunction "4_4") (pintype "passive"))
    )
    (net (code "86") (name "unconnected-(U4-NC-Pad4)") (class "Default")
      (node (ref "U4") (pin "4") (pinfunction "NC_4") (pintype "passive+no_connect"))
    )
  )
)
